# Sheet_CL-STM32.net
KiCad netlist of a schematic drawn in Altium Designer
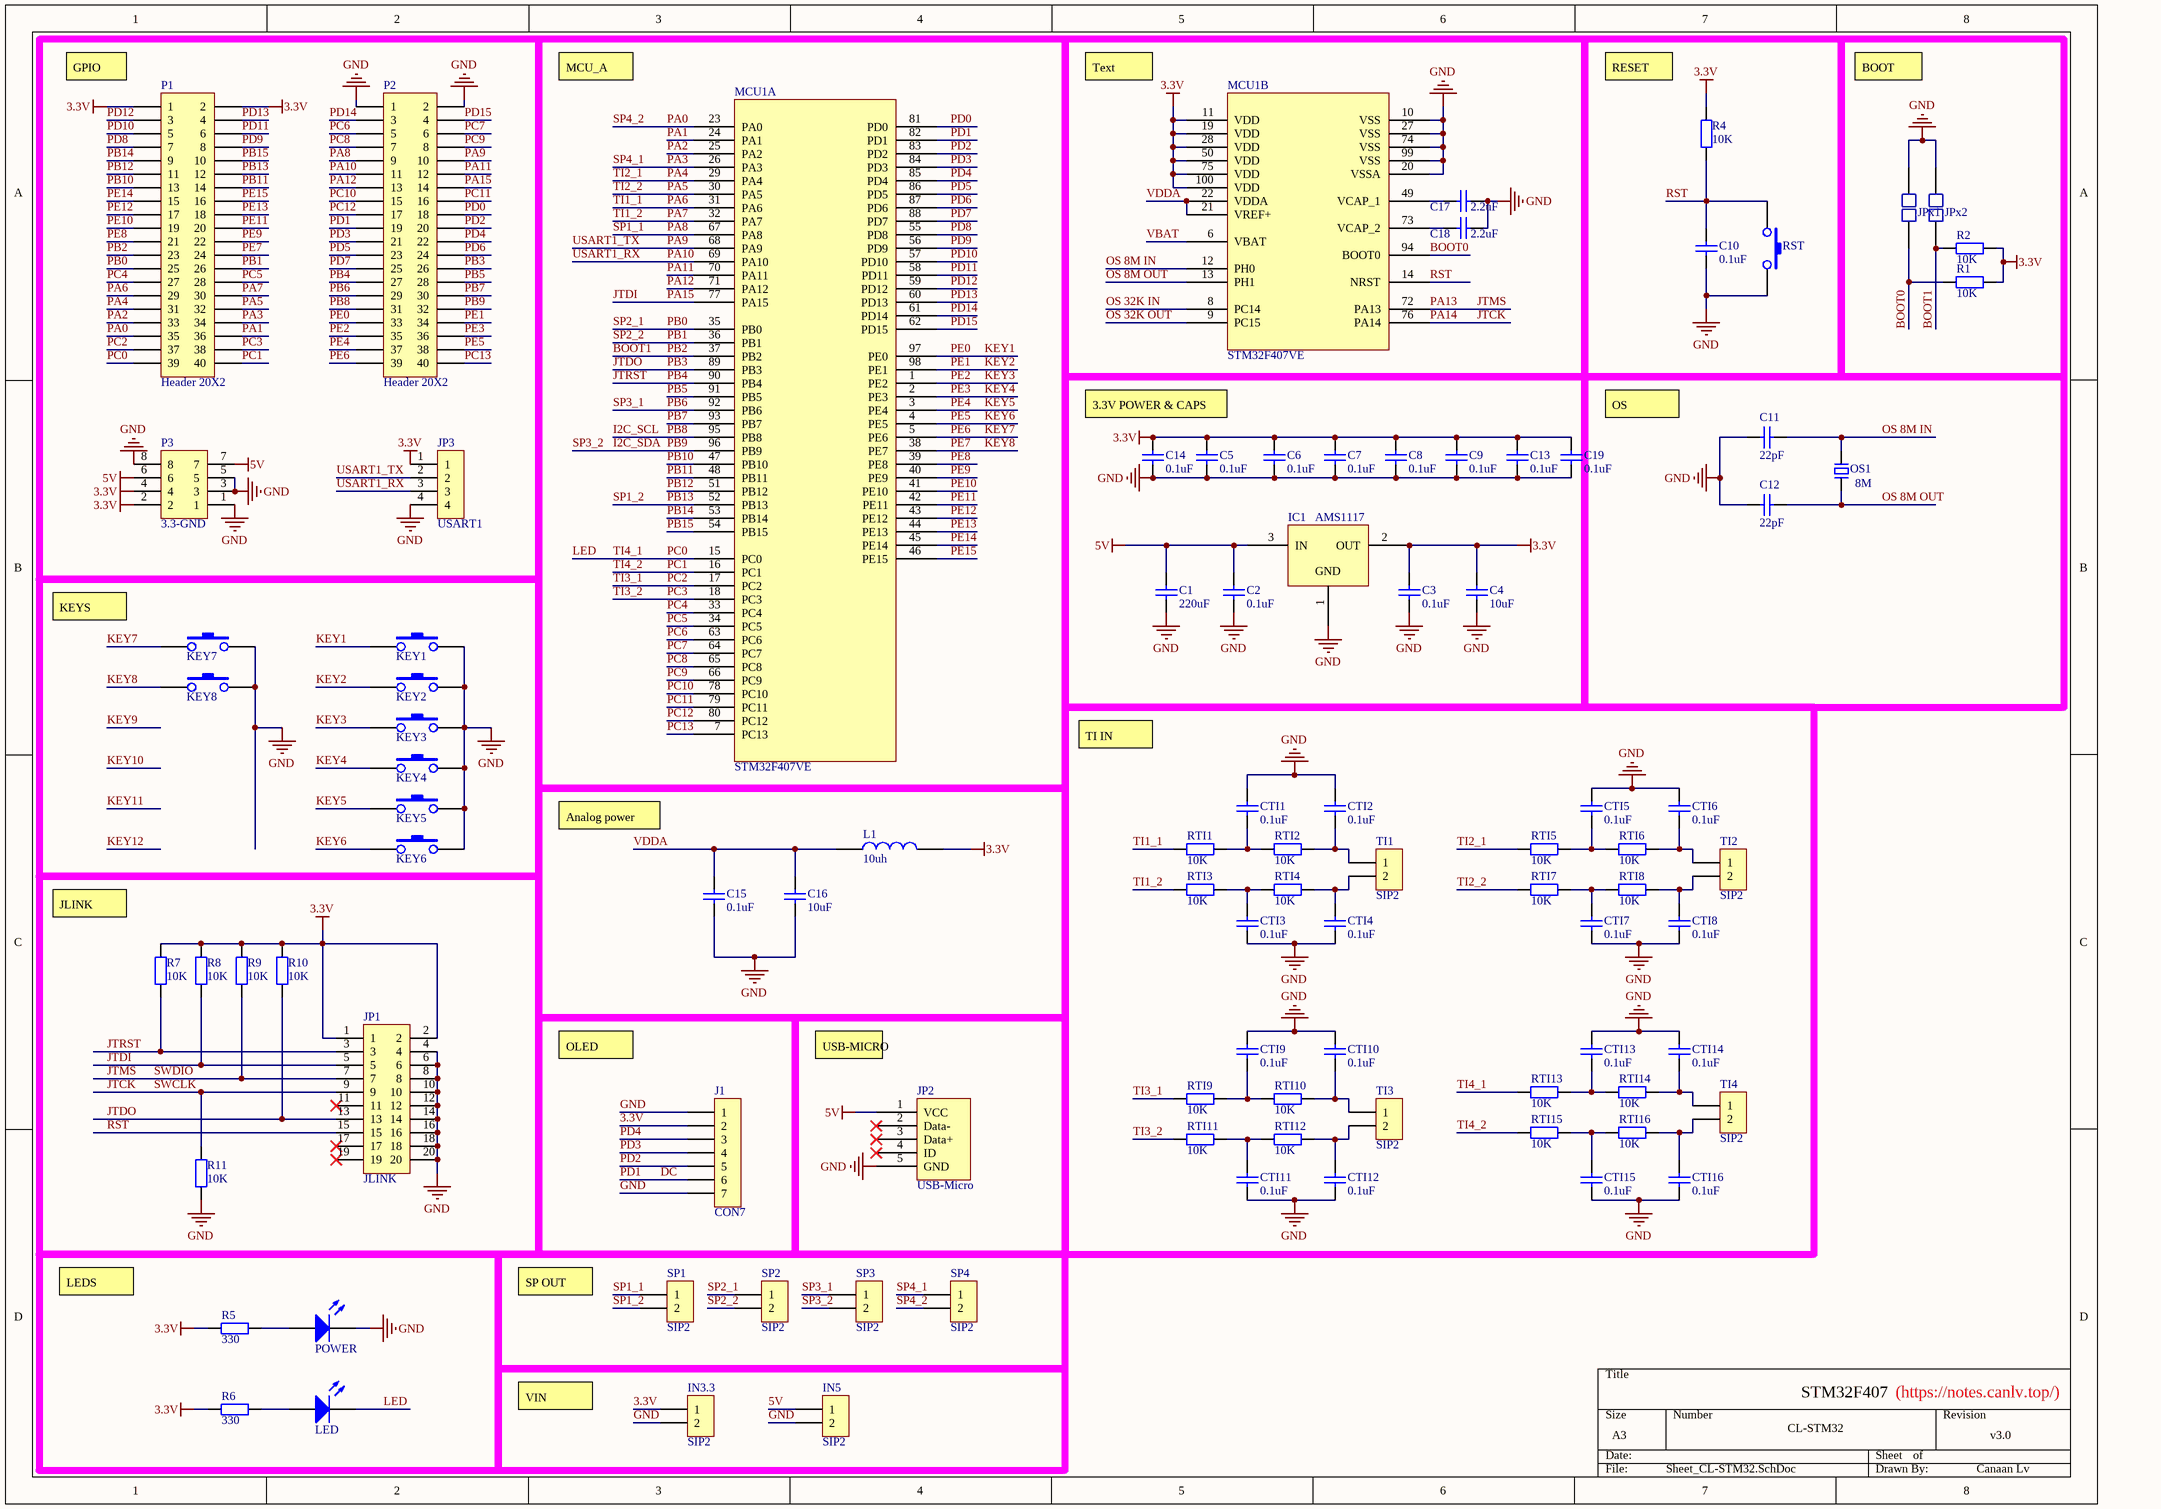
[diagram p0: Sheet_CL-STM32.SchDoc]

(export (version "E")
  (design (tool "Eeschema 10.0.6"))
  (components
    (comp (ref "C1") (value "220uF") (footprint "0805") (libsource (lib "器件库") (part "Cap1")))
    (comp (ref "C2") (value "0.1uF") (footprint "0603") (libsource (lib "器件库") (part "Cap1")))
    (comp (ref "C3") (value "0.1uF") (footprint "0603") (libsource (lib "器件库") (part "Cap1")))
    (comp (ref "C4") (value "10uF") (footprint "0603") (libsource (lib "器件库") (part "Cap1")))
    (comp (ref "C5") (value "0.1uF") (footprint "0603") (libsource (lib "器件库") (part "Cap1")))
    (comp (ref "C6") (value "0.1uF") (footprint "0603") (libsource (lib "器件库") (part "Cap1")))
    (comp (ref "C7") (value "0.1uF") (footprint "0603") (libsource (lib "器件库") (part "Cap1")))
    (comp (ref "C8") (value "0.1uF") (footprint "0603") (libsource (lib "器件库") (part "Cap1")))
    (comp (ref "C9") (value "0.1uF") (footprint "0603") (libsource (lib "器件库") (part "Cap1")))
    (comp (ref "C10") (value "0.1uF") (footprint "0603") (libsource (lib "器件库") (part "Cap1")))
    (comp (ref "C11") (value "22pF") (footprint "0603") (libsource (lib "器件库") (part "Cap1")))
    (comp (ref "C12") (value "22pF") (footprint "0603") (libsource (lib "器件库") (part "Cap1")))
    (comp (ref "C13") (value "0.1uF") (footprint "0603") (libsource (lib "元件") (part "Cap1")))
    (comp (ref "C14") (value "0.1uF") (footprint "0603") (libsource (lib "元件") (part "Cap1")))
    (comp (ref "C15") (value "0.1uF") (footprint "0603") (libsource (lib "器件库") (part "Cap1")))
    (comp (ref "C16") (value "10uF") (footprint "0603") (libsource (lib "器件库") (part "Cap1")))
    (comp (ref "C17") (value "2.2uF") (footprint "0603") (libsource (lib "元件") (part "Cap1")))
    (comp (ref "C18") (value "2.2uF") (footprint "0603") (libsource (lib "元件") (part "Cap1")))
    (comp (ref "C19") (value "0.1uF") (footprint "0603") (libsource (lib "元件") (part "Cap1")))
    (comp (ref "CTI1") (value "0.1uF") (footprint "0603") (libsource (lib "元件") (part "Cap1")))
    (comp (ref "CTI2") (value "0.1uF") (footprint "0603") (libsource (lib "元件") (part "Cap1")))
    (comp (ref "CTI3") (value "0.1uF") (footprint "0603") (libsource (lib "元件") (part "Cap1")))
    (comp (ref "CTI4") (value "0.1uF") (footprint "0603") (libsource (lib "元件") (part "Cap1")))
    (comp (ref "CTI5") (value "0.1uF") (footprint "0603") (libsource (lib "元件") (part "Cap1")))
    (comp (ref "CTI6") (value "0.1uF") (footprint "0603") (libsource (lib "元件") (part "Cap1")))
    (comp (ref "CTI7") (value "0.1uF") (footprint "0603") (libsource (lib "元件") (part "Cap1")))
    (comp (ref "CTI8") (value "0.1uF") (footprint "0603") (libsource (lib "元件") (part "Cap1")))
    (comp (ref "CTI9") (value "0.1uF") (footprint "0603") (libsource (lib "元件") (part "Cap1")))
    (comp (ref "CTI10") (value "0.1uF") (footprint "0603") (libsource (lib "元件") (part "Cap1")))
    (comp (ref "CTI11") (value "0.1uF") (footprint "0603") (libsource (lib "元件") (part "Cap1")))
    (comp (ref "CTI12") (value "0.1uF") (footprint "0603") (libsource (lib "元件") (part "Cap1")))
    (comp (ref "CTI13") (value "0.1uF") (footprint "0603") (libsource (lib "元件") (part "Cap1")))
    (comp (ref "CTI14") (value "0.1uF") (footprint "0603") (libsource (lib "元件") (part "Cap1")))
    (comp (ref "CTI15") (value "0.1uF") (footprint "0603") (libsource (lib "元件") (part "Cap1")))
    (comp (ref "CTI16") (value "0.1uF") (footprint "0603") (libsource (lib "元件") (part "Cap1")))
    (comp (ref "IC1") (value "AMS1117") (footprint "AMS1117") (libsource (lib "器件库") (part "CJA1117")))
    (comp (ref "IN3.3")
      (value "SIP2")
      (footprint "2.54XH接插件2P")
      (description "jointbar")
      (libsource (lib "接口与插座") (part "SIP2"))
    )
    (comp (ref "IN5")
      (value "SIP2")
      (footprint "2.54XH接插件2P")
      (description "jointbar")
      (libsource (lib "接口与插座") (part "SIP2"))
    )
    (comp (ref "J1")
      (value "CON7")
      (footprint "2.54排针1X7")
      (description "Connector")
      (libsource (lib "插件") (part "CON7"))
    )
    (comp (ref "JP1") (value "JLINK") (footprint "2.54简易牛角座20p") (libsource (lib "接插件") (part "PIN-20")))
    (comp (ref "JP2")
      (value "USB-Micro")
      (footprint "USB-MICRO贴片")
      (libsource (lib "接插件") (part "USB-Micro"))
    )
    (comp (ref "JP3") (value "USART1") (footprint "2.54排针1X4") (libsource (lib "接插件") (part "SIP-4")))
    (comp (ref "JPx1") (value "Select") (footprint "选择焊点-0402") (libsource (lib "元件") (part "Select")))
    (comp (ref "JPx2") (value "Select") (footprint "选择焊点-0402") (libsource (lib "元件") (part "Select")))
    (comp (ref "KEY1") (value "按键") (footprint "SWT6*3") (libsource (lib "器件库") (part "按键")))
    (comp (ref "KEY2") (value "按键") (footprint "SWT6*3") (libsource (lib "器件库") (part "按键")))
    (comp (ref "KEY3") (value "按键") (footprint "SWT6*3") (libsource (lib "器件库") (part "按键")))
    (comp (ref "KEY4") (value "按键") (footprint "SWT6*3") (libsource (lib "器件库") (part "按键")))
    (comp (ref "KEY5") (value "按键") (footprint "SWT6*3") (libsource (lib "器件库") (part "按键")))
    (comp (ref "KEY6") (value "按键") (footprint "SWT6*3") (libsource (lib "器件库") (part "按键")))
    (comp (ref "KEY7") (value "按键") (footprint "SWT6*3") (libsource (lib "器件库") (part "按键")))
    (comp (ref "KEY8") (value "按键") (footprint "SWT6*3") (libsource (lib "元件") (part "按键")))
    (comp (ref "L1") (value "10uh") (footprint "0603-res") (libsource (lib "器件库") (part "电感")))
    (comp (ref "LED") (value "LED") (footprint "D0603") (libsource (lib "器件库") (part "LED")))
    (comp (ref "MCU1")
      (value "STM32F407VE")
      (footprint "F-QFP14x14-G100/P.5N")
      (libsource (lib "元件") (part "STM32F407VE"))
    )
    (comp (ref "OS1")
      (value "~")
      (footprint "HC-49S")
      (fields (field (name "ALTIUM_UNNAMED_1") "8M"))
      (libsource (lib "常用2") (part "JT"))
    )
    (comp (ref "P1")
      (value "Header 20X2")
      (footprint "2.54排针2X20")
      (description "Header, 20-Pin, Dual row")
      (fields (field (name "PUBLISHER") "Altium Limited"))
      (libsource (lib "元件") (part "Header 20X2"))
    )
    (comp (ref "P2")
      (value "Header 20X2")
      (footprint "2.54排针2X20")
      (description "Header, 20-Pin, Dual row")
      (fields (field (name "PUBLISHER") "Altium Limited"))
      (libsource (lib "元件") (part "Header 20X2"))
    )
    (comp (ref "P3") (value "3.3-GND") (footprint "2.54排针2X4") (libsource (lib "接插件") (part "PIN-8")))
    (comp (ref "POWER") (value "LED") (footprint "D0603") (libsource (lib "器件库") (part "LED")))
    (comp (ref "R1") (value "10K") (footprint "0603-res") (libsource (lib "") (part "Res_1")))
    (comp (ref "R2") (value "10K") (footprint "0603-res") (libsource (lib "") (part "Res_1")))
    (comp (ref "R4") (value "10K") (footprint "0603-res") (libsource (lib "") (part "Res_1")))
    (comp (ref "R5") (value "330") (footprint "0603-res") (libsource (lib "器件库") (part "Res")))
    (comp (ref "R6") (value "330") (footprint "0603-res") (libsource (lib "器件库") (part "Res")))
    (comp (ref "R7") (value "10K") (footprint "0603-res") (libsource (lib "") (part "Res_1")))
    (comp (ref "R8") (value "10K") (footprint "0603-res") (libsource (lib "") (part "Res_1")))
    (comp (ref "R9") (value "10K") (footprint "0603-res") (libsource (lib "") (part "Res_1")))
    (comp (ref "R10") (value "10K") (footprint "0603-res") (libsource (lib "") (part "Res_1")))
    (comp (ref "R11") (value "10K") (footprint "0603-res") (libsource (lib "") (part "Res_1")))
    (comp (ref "RST") (value "按键") (footprint "按键微动开关2") (libsource (lib "器件库") (part "按键")))
    (comp (ref "RTI1") (value "10K") (footprint "0603-res") (libsource (lib "元件") (part "Res")))
    (comp (ref "RTI2") (value "10K") (footprint "0603-res") (libsource (lib "元件") (part "Res")))
    (comp (ref "RTI3") (value "10K") (footprint "0603-res") (libsource (lib "元件") (part "Res")))
    (comp (ref "RTI4") (value "10K") (footprint "0603-res") (libsource (lib "元件") (part "Res")))
    (comp (ref "RTI5") (value "10K") (footprint "0603-res") (libsource (lib "元件") (part "Res")))
    (comp (ref "RTI6") (value "10K") (footprint "0603-res") (libsource (lib "元件") (part "Res")))
    (comp (ref "RTI7") (value "10K") (footprint "0603-res") (libsource (lib "元件") (part "Res")))
    (comp (ref "RTI8") (value "10K") (footprint "0603-res") (libsource (lib "元件") (part "Res")))
    (comp (ref "RTI9") (value "10K") (footprint "0603-res") (libsource (lib "元件") (part "Res")))
    (comp (ref "RTI10") (value "10K") (footprint "0603-res") (libsource (lib "元件") (part "Res")))
    (comp (ref "RTI11") (value "10K") (footprint "0603-res") (libsource (lib "元件") (part "Res")))
    (comp (ref "RTI12") (value "10K") (footprint "0603-res") (libsource (lib "元件") (part "Res")))
    (comp (ref "RTI13") (value "10K") (footprint "0603-res") (libsource (lib "元件") (part "Res")))
    (comp (ref "RTI14") (value "10K") (footprint "0603-res") (libsource (lib "元件") (part "Res")))
    (comp (ref "RTI15") (value "10K") (footprint "0603-res") (libsource (lib "元件") (part "Res")))
    (comp (ref "RTI16") (value "10K") (footprint "0603-res") (libsource (lib "元件") (part "Res")))
    (comp (ref "SP1")
      (value "SIP2")
      (footprint "2.54XH接插件2P")
      (description "jointbar")
      (libsource (lib "接口与插座") (part "SIP2"))
    )
    (comp (ref "SP2")
      (value "SIP2")
      (footprint "2.54XH接插件2P")
      (description "jointbar")
      (libsource (lib "接口与插座") (part "SIP2"))
    )
    (comp (ref "SP3")
      (value "SIP2")
      (footprint "2.54XH接插件2P")
      (description "jointbar")
      (libsource (lib "接口与插座") (part "SIP2"))
    )
    (comp (ref "SP4")
      (value "SIP2")
      (footprint "2.54XH接插件2P")
      (description "jointbar")
      (libsource (lib "接口与插座") (part "SIP2"))
    )
    (comp (ref "TI1")
      (value "SIP2")
      (footprint "2.54XH接插件2P")
      (description "jointbar")
      (libsource (lib "接口与插座") (part "SIP2"))
    )
    (comp (ref "TI2")
      (value "SIP2")
      (footprint "2.54XH接插件2P")
      (description "jointbar")
      (libsource (lib "接口与插座") (part "SIP2"))
    )
    (comp (ref "TI3")
      (value "SIP2")
      (footprint "2.54XH接插件2P")
      (description "jointbar")
      (libsource (lib "接口与插座") (part "SIP2"))
    )
    (comp (ref "TI4")
      (value "SIP2")
      (footprint "2.54XH接插件2P")
      (description "jointbar")
      (libsource (lib "接口与插座") (part "SIP2"))
    )
  )
  (nets
    (net (code "1") (name "/BOOT0") (class "Default")
      (node (ref "JPx1") (pin "1") (pinfunction "1_1") (pintype "passive"))
      (node (ref "MCU1") (pin "94") (pinfunction "BOOT0_94") (pintype "passive"))
      (node (ref "R1") (pin "2") (pinfunction "2_2") (pintype "passive"))
    )
    (net (code "2") (name "/BOOT1") (class "Default")
      (node (ref "JPx2") (pin "1") (pinfunction "1_1") (pintype "passive"))
      (node (ref "MCU1") (pin "37") (pinfunction "PB2_37") (pintype "passive"))
      (node (ref "P1") (pin "23") (pinfunction "23_23") (pintype "passive"))
      (node (ref "R2") (pin "2") (pinfunction "2_2") (pintype "passive"))
    )
    (net (code "3") (name "/DC") (class "Default")
      (node (ref "J1") (pin "6") (pinfunction "6_6") (pintype "passive"))
      (node (ref "MCU1") (pin "82") (pinfunction "PD1_82") (pintype "passive"))
      (node (ref "P2") (pin "19") (pinfunction "19_19") (pintype "passive"))
    )
    (net (code "4") (name "/I2C_SCL") (class "Default")
      (node (ref "MCU1") (pin "95") (pinfunction "PB8_95") (pintype "passive"))
      (node (ref "P2") (pin "31") (pinfunction "31_31") (pintype "passive"))
    )
    (net (code "5") (name "/I2C_SDA") (class "Default")
      (node (ref "MCU1") (pin "96") (pinfunction "PB9_96") (pintype "passive"))
      (node (ref "P2") (pin "32") (pinfunction "32_32") (pintype "passive"))
      (node (ref "SP3") (pin "2") (pinfunction "2_2") (pintype "passive"))
    )
    (net (code "6") (name "/JTCK") (class "Default")
      (node (ref "JP1") (pin "9") (pinfunction "9_9") (pintype "passive"))
      (node (ref "MCU1") (pin "76") (pinfunction "PA14_76") (pintype "passive"))
      (node (ref "R11") (pin "2") (pinfunction "2_2") (pintype "passive"))
    )
    (net (code "7") (name "/JTDI") (class "Default")
      (node (ref "JP1") (pin "5") (pinfunction "5_5") (pintype "passive"))
      (node (ref "MCU1") (pin "77") (pinfunction "PA15_77") (pintype "passive"))
      (node (ref "P2") (pin "14") (pinfunction "14_14") (pintype "passive"))
      (node (ref "R8") (pin "1") (pinfunction "1_1") (pintype "passive"))
    )
    (net (code "8") (name "/JTDO") (class "Default")
      (node (ref "JP1") (pin "13") (pinfunction "13_13") (pintype "passive"))
      (node (ref "MCU1") (pin "89") (pinfunction "PB3_89") (pintype "passive"))
      (node (ref "P2") (pin "26") (pinfunction "26_26") (pintype "passive"))
      (node (ref "R10") (pin "1") (pinfunction "1_1") (pintype "passive"))
    )
    (net (code "9") (name "/JTMS") (class "Default")
      (node (ref "JP1") (pin "7") (pinfunction "7_7") (pintype "passive"))
      (node (ref "MCU1") (pin "72") (pinfunction "PA13_72") (pintype "passive"))
      (node (ref "R9") (pin "1") (pinfunction "1_1") (pintype "passive"))
    )
    (net (code "10") (name "/JTRST") (class "Default")
      (node (ref "JP1") (pin "3") (pinfunction "3_3") (pintype "passive"))
      (node (ref "MCU1") (pin "90") (pinfunction "PB4_90") (pintype "passive"))
      (node (ref "P2") (pin "27") (pinfunction "27_27") (pintype "passive"))
      (node (ref "R7") (pin "1") (pinfunction "1_1") (pintype "passive"))
    )
    (net (code "11") (name "/KEY1") (class "Default")
      (node (ref "KEY1") (pin "1") (pinfunction "1_1") (pintype "passive"))
      (node (ref "MCU1") (pin "97") (pinfunction "PE0_97") (pintype "passive"))
      (node (ref "P2") (pin "33") (pinfunction "33_33") (pintype "passive"))
    )
    (net (code "12") (name "/KEY2") (class "Default")
      (node (ref "KEY2") (pin "1") (pinfunction "1_1") (pintype "passive"))
      (node (ref "MCU1") (pin "98") (pinfunction "PE1_98") (pintype "passive"))
      (node (ref "P2") (pin "34") (pinfunction "34_34") (pintype "passive"))
    )
    (net (code "13") (name "/KEY3") (class "Default")
      (node (ref "KEY3") (pin "1") (pinfunction "1_1") (pintype "passive"))
      (node (ref "MCU1") (pin "1") (pinfunction "PE2_1") (pintype "passive"))
      (node (ref "P2") (pin "35") (pinfunction "35_35") (pintype "passive"))
    )
    (net (code "14") (name "/KEY4") (class "Default")
      (node (ref "KEY4") (pin "1") (pinfunction "1_1") (pintype "passive"))
      (node (ref "MCU1") (pin "2") (pinfunction "PE3_2") (pintype "passive"))
      (node (ref "P2") (pin "36") (pinfunction "36_36") (pintype "passive"))
    )
    (net (code "15") (name "/KEY5") (class "Default")
      (node (ref "KEY5") (pin "1") (pinfunction "1_1") (pintype "passive"))
      (node (ref "MCU1") (pin "3") (pinfunction "PE4_3") (pintype "passive"))
      (node (ref "P2") (pin "37") (pinfunction "37_37") (pintype "passive"))
    )
    (net (code "16") (name "/KEY6") (class "Default")
      (node (ref "KEY6") (pin "1") (pinfunction "1_1") (pintype "passive"))
      (node (ref "MCU1") (pin "4") (pinfunction "PE5_4") (pintype "passive"))
      (node (ref "P2") (pin "38") (pinfunction "38_38") (pintype "passive"))
    )
    (net (code "17") (name "/KEY7") (class "Default")
      (node (ref "KEY7") (pin "1") (pinfunction "1_1") (pintype "passive"))
      (node (ref "MCU1") (pin "5") (pinfunction "PE6_5") (pintype "passive"))
      (node (ref "P2") (pin "39") (pinfunction "39_39") (pintype "passive"))
    )
    (net (code "18") (name "/KEY8") (class "Default")
      (node (ref "KEY8") (pin "1") (pinfunction "1_1") (pintype "passive"))
      (node (ref "MCU1") (pin "38") (pinfunction "PE7_38") (pintype "passive"))
      (node (ref "P1") (pin "24") (pinfunction "24_24") (pintype "passive"))
    )
    (net (code "23") (name "/LED") (class "Default")
      (node (ref "LED") (pin "2") (pinfunction "K_2") (pintype "passive"))
      (node (ref "MCU1") (pin "15") (pinfunction "PC0_15") (pintype "passive"))
      (node (ref "P1") (pin "39") (pinfunction "39_39") (pintype "passive"))
      (node (ref "RTI13") (pin "1") (pinfunction "1_1") (pintype "passive"))
    )
    (net (code "24") (name "/OS 8M IN") (class "Default")
      (node (ref "C11") (pin "1") (pinfunction "1_1") (pintype "passive"))
      (node (ref "MCU1") (pin "12") (pinfunction "PH0_12") (pintype "passive"))
      (node (ref "OS1") (pin "2") (pinfunction "2_2") (pintype "passive"))
    )
    (net (code "25") (name "/OS 8M OUT") (class "Default")
      (node (ref "C12") (pin "1") (pinfunction "1_1") (pintype "passive"))
      (node (ref "MCU1") (pin "13") (pinfunction "PH1_13") (pintype "passive"))
      (node (ref "OS1") (pin "1") (pinfunction "1_1") (pintype "passive"))
    )
    (net (code "26") (name "/OS 32K IN") (class "Default")
      (node (ref "MCU1") (pin "8") (pinfunction "PC14_8") (pintype "passive"))
    )
    (net (code "27") (name "/OS 32K OUT") (class "Default")
      (node (ref "MCU1") (pin "9") (pinfunction "PC15_9") (pintype "passive"))
    )
    (net (code "28") (name "/PA0") (class "Default")
      (node (ref "MCU1") (pin "23") (pinfunction "PA0_23") (pintype "passive"))
      (node (ref "P1") (pin "35") (pinfunction "35_35") (pintype "passive"))
      (node (ref "SP4") (pin "2") (pinfunction "2_2") (pintype "passive"))
    )
    (net (code "29") (name "/PA1") (class "Default")
      (node (ref "MCU1") (pin "24") (pinfunction "PA1_24") (pintype "passive"))
      (node (ref "P1") (pin "36") (pinfunction "36_36") (pintype "passive"))
    )
    (net (code "30") (name "/PA2") (class "Default")
      (node (ref "MCU1") (pin "25") (pinfunction "PA2_25") (pintype "passive"))
      (node (ref "P1") (pin "33") (pinfunction "33_33") (pintype "passive"))
    )
    (net (code "31") (name "/PA3") (class "Default")
      (node (ref "MCU1") (pin "26") (pinfunction "PA3_26") (pintype "passive"))
      (node (ref "P1") (pin "34") (pinfunction "34_34") (pintype "passive"))
      (node (ref "SP4") (pin "1") (pinfunction "1_1") (pintype "passive"))
    )
    (net (code "32") (name "/PA4") (class "Default")
      (node (ref "MCU1") (pin "29") (pinfunction "PA4_29") (pintype "passive"))
      (node (ref "P1") (pin "31") (pinfunction "31_31") (pintype "passive"))
      (node (ref "RTI5") (pin "1") (pinfunction "1_1") (pintype "passive"))
    )
    (net (code "33") (name "/PA5") (class "Default")
      (node (ref "MCU1") (pin "30") (pinfunction "PA5_30") (pintype "passive"))
      (node (ref "P1") (pin "32") (pinfunction "32_32") (pintype "passive"))
      (node (ref "RTI7") (pin "1") (pinfunction "1_1") (pintype "passive"))
    )
    (net (code "34") (name "/PA6") (class "Default")
      (node (ref "MCU1") (pin "31") (pinfunction "PA6_31") (pintype "passive"))
      (node (ref "P1") (pin "29") (pinfunction "29_29") (pintype "passive"))
      (node (ref "RTI1") (pin "1") (pinfunction "1_1") (pintype "passive"))
    )
    (net (code "35") (name "/PA7") (class "Default")
      (node (ref "MCU1") (pin "32") (pinfunction "PA7_32") (pintype "passive"))
      (node (ref "P1") (pin "30") (pinfunction "30_30") (pintype "passive"))
      (node (ref "RTI3") (pin "1") (pinfunction "1_1") (pintype "passive"))
    )
    (net (code "36") (name "/PA8") (class "Default")
      (node (ref "MCU1") (pin "67") (pinfunction "PA8_67") (pintype "passive"))
      (node (ref "P2") (pin "9") (pinfunction "9_9") (pintype "passive"))
      (node (ref "SP1") (pin "1") (pinfunction "1_1") (pintype "passive"))
    )
    (net (code "37") (name "/PA9") (class "Default")
      (node (ref "JP3") (pin "2") (pinfunction "2_2") (pintype "passive"))
      (node (ref "MCU1") (pin "68") (pinfunction "PA9_68") (pintype "passive"))
      (node (ref "P2") (pin "10") (pinfunction "10_10") (pintype "passive"))
    )
    (net (code "38") (name "/PA10") (class "Default")
      (node (ref "JP3") (pin "3") (pinfunction "3_3") (pintype "passive"))
      (node (ref "MCU1") (pin "69") (pinfunction "PA10_69") (pintype "passive"))
      (node (ref "P2") (pin "11") (pinfunction "11_11") (pintype "passive"))
    )
    (net (code "39") (name "/PA11") (class "Default")
      (node (ref "MCU1") (pin "70") (pinfunction "PA11_70") (pintype "passive"))
      (node (ref "P2") (pin "12") (pinfunction "12_12") (pintype "passive"))
    )
    (net (code "40") (name "/PA12") (class "Default")
      (node (ref "MCU1") (pin "71") (pinfunction "PA12_71") (pintype "passive"))
      (node (ref "P2") (pin "13") (pinfunction "13_13") (pintype "passive"))
    )
    (net (code "41") (name "/PB0") (class "Default")
      (node (ref "MCU1") (pin "35") (pinfunction "PB0_35") (pintype "passive"))
      (node (ref "P1") (pin "25") (pinfunction "25_25") (pintype "passive"))
      (node (ref "SP2") (pin "1") (pinfunction "1_1") (pintype "passive"))
    )
    (net (code "42") (name "/PB1") (class "Default")
      (node (ref "MCU1") (pin "36") (pinfunction "PB1_36") (pintype "passive"))
      (node (ref "P1") (pin "26") (pinfunction "26_26") (pintype "passive"))
      (node (ref "SP2") (pin "2") (pinfunction "2_2") (pintype "passive"))
    )
    (net (code "43") (name "/PB5") (class "Default")
      (node (ref "MCU1") (pin "91") (pinfunction "PB5_91") (pintype "passive"))
      (node (ref "P2") (pin "28") (pinfunction "28_28") (pintype "passive"))
    )
    (net (code "44") (name "/PB6") (class "Default")
      (node (ref "MCU1") (pin "92") (pinfunction "PB6_92") (pintype "passive"))
      (node (ref "P2") (pin "29") (pinfunction "29_29") (pintype "passive"))
      (node (ref "SP3") (pin "1") (pinfunction "1_1") (pintype "passive"))
    )
    (net (code "45") (name "/PB7") (class "Default")
      (node (ref "MCU1") (pin "93") (pinfunction "PB7_93") (pintype "passive"))
      (node (ref "P2") (pin "30") (pinfunction "30_30") (pintype "passive"))
    )
    (net (code "46") (name "/PB10") (class "Default")
      (node (ref "MCU1") (pin "47") (pinfunction "PB10_47") (pintype "passive"))
      (node (ref "P1") (pin "13") (pinfunction "13_13") (pintype "passive"))
    )
    (net (code "47") (name "/PB11") (class "Default")
      (node (ref "MCU1") (pin "48") (pinfunction "PB11_48") (pintype "passive"))
      (node (ref "P1") (pin "14") (pinfunction "14_14") (pintype "passive"))
    )
    (net (code "48") (name "/PB12") (class "Default")
      (node (ref "MCU1") (pin "51") (pinfunction "PB12_51") (pintype "passive"))
      (node (ref "P1") (pin "11") (pinfunction "11_11") (pintype "passive"))
    )
    (net (code "49") (name "/PB13") (class "Default")
      (node (ref "MCU1") (pin "52") (pinfunction "PB13_52") (pintype "passive"))
      (node (ref "P1") (pin "12") (pinfunction "12_12") (pintype "passive"))
      (node (ref "SP1") (pin "2") (pinfunction "2_2") (pintype "passive"))
    )
    (net (code "50") (name "/PB14") (class "Default")
      (node (ref "MCU1") (pin "53") (pinfunction "PB14_53") (pintype "passive"))
      (node (ref "P1") (pin "9") (pinfunction "9_9") (pintype "passive"))
    )
    (net (code "51") (name "/PB15") (class "Default")
      (node (ref "MCU1") (pin "54") (pinfunction "PB15_54") (pintype "passive"))
      (node (ref "P1") (pin "10") (pinfunction "10_10") (pintype "passive"))
    )
    (net (code "52") (name "/PC1") (class "Default")
      (node (ref "MCU1") (pin "16") (pinfunction "PC1_16") (pintype "passive"))
      (node (ref "P1") (pin "40") (pinfunction "40_40") (pintype "passive"))
      (node (ref "RTI15") (pin "1") (pinfunction "1_1") (pintype "passive"))
    )
    (net (code "53") (name "/PC2") (class "Default")
      (node (ref "MCU1") (pin "17") (pinfunction "PC2_17") (pintype "passive"))
      (node (ref "P1") (pin "37") (pinfunction "37_37") (pintype "passive"))
      (node (ref "RTI9") (pin "1") (pinfunction "1_1") (pintype "passive"))
    )
    (net (code "54") (name "/PC3") (class "Default")
      (node (ref "MCU1") (pin "18") (pinfunction "PC3_18") (pintype "passive"))
      (node (ref "P1") (pin "38") (pinfunction "38_38") (pintype "passive"))
      (node (ref "RTI11") (pin "1") (pinfunction "1_1") (pintype "passive"))
    )
    (net (code "55") (name "/PC4") (class "Default")
      (node (ref "MCU1") (pin "33") (pinfunction "PC4_33") (pintype "passive"))
      (node (ref "P1") (pin "27") (pinfunction "27_27") (pintype "passive"))
    )
    (net (code "56") (name "/PC5") (class "Default")
      (node (ref "MCU1") (pin "34") (pinfunction "PC5_34") (pintype "passive"))
      (node (ref "P1") (pin "28") (pinfunction "28_28") (pintype "passive"))
    )
    (net (code "57") (name "/PC6") (class "Default")
      (node (ref "MCU1") (pin "63") (pinfunction "PC6_63") (pintype "passive"))
      (node (ref "P2") (pin "5") (pinfunction "5_5") (pintype "passive"))
    )
    (net (code "58") (name "/PC7") (class "Default")
      (node (ref "MCU1") (pin "64") (pinfunction "PC7_64") (pintype "passive"))
      (node (ref "P2") (pin "6") (pinfunction "6_6") (pintype "passive"))
    )
    (net (code "59") (name "/PC8") (class "Default")
      (node (ref "MCU1") (pin "65") (pinfunction "PC8_65") (pintype "passive"))
      (node (ref "P2") (pin "7") (pinfunction "7_7") (pintype "passive"))
    )
    (net (code "60") (name "/PC9") (class "Default")
      (node (ref "MCU1") (pin "66") (pinfunction "PC9_66") (pintype "passive"))
      (node (ref "P2") (pin "8") (pinfunction "8_8") (pintype "passive"))
    )
    (net (code "61") (name "/PC10") (class "Default")
      (node (ref "MCU1") (pin "78") (pinfunction "PC10_78") (pintype "passive"))
      (node (ref "P2") (pin "15") (pinfunction "15_15") (pintype "passive"))
    )
    (net (code "62") (name "/PC11") (class "Default")
      (node (ref "MCU1") (pin "79") (pinfunction "PC11_79") (pintype "passive"))
      (node (ref "P2") (pin "16") (pinfunction "16_16") (pintype "passive"))
    )
    (net (code "63") (name "/PC12") (class "Default")
      (node (ref "MCU1") (pin "80") (pinfunction "PC12_80") (pintype "passive"))
      (node (ref "P2") (pin "17") (pinfunction "17_17") (pintype "passive"))
    )
    (net (code "64") (name "/PC13") (class "Default")
      (node (ref "MCU1") (pin "7") (pinfunction "PC13_7") (pintype "passive"))
      (node (ref "P2") (pin "40") (pinfunction "40_40") (pintype "passive"))
    )
    (net (code "65") (name "/PD0") (class "Default")
      (node (ref "MCU1") (pin "81") (pinfunction "PD0_81") (pintype "passive"))
      (node (ref "P2") (pin "18") (pinfunction "18_18") (pintype "passive"))
    )
    (net (code "66") (name "/PD2") (class "Default")
      (node (ref "J1") (pin "5") (pinfunction "5_5") (pintype "passive"))
      (node (ref "MCU1") (pin "83") (pinfunction "PD2_83") (pintype "passive"))
      (node (ref "P2") (pin "20") (pinfunction "20_20") (pintype "passive"))
    )
    (net (code "67") (name "/PD3") (class "Default")
      (node (ref "J1") (pin "4") (pinfunction "4_4") (pintype "passive"))
      (node (ref "MCU1") (pin "84") (pinfunction "PD3_84") (pintype "passive"))
      (node (ref "P2") (pin "21") (pinfunction "21_21") (pintype "passive"))
    )
    (net (code "68") (name "/PD4") (class "Default")
      (node (ref "J1") (pin "3") (pinfunction "3_3") (pintype "passive"))
      (node (ref "MCU1") (pin "85") (pinfunction "PD4_85") (pintype "passive"))
      (node (ref "P2") (pin "22") (pinfunction "22_22") (pintype "passive"))
    )
    (net (code "69") (name "/PD5") (class "Default")
      (node (ref "MCU1") (pin "86") (pinfunction "PD5_86") (pintype "passive"))
      (node (ref "P2") (pin "23") (pinfunction "23_23") (pintype "passive"))
    )
    (net (code "70") (name "/PD6") (class "Default")
      (node (ref "MCU1") (pin "87") (pinfunction "PD6_87") (pintype "passive"))
      (node (ref "P2") (pin "24") (pinfunction "24_24") (pintype "passive"))
    )
    (net (code "71") (name "/PD7") (class "Default")
      (node (ref "MCU1") (pin "88") (pinfunction "PD7_88") (pintype "passive"))
      (node (ref "P2") (pin "25") (pinfunction "25_25") (pintype "passive"))
    )
    (net (code "72") (name "/PD8") (class "Default")
      (node (ref "MCU1") (pin "55") (pinfunction "PD8_55") (pintype "passive"))
      (node (ref "P1") (pin "7") (pinfunction "7_7") (pintype "passive"))
    )
    (net (code "73") (name "/PD9") (class "Default")
      (node (ref "MCU1") (pin "56") (pinfunction "PD9_56") (pintype "passive"))
      (node (ref "P1") (pin "8") (pinfunction "8_8") (pintype "passive"))
    )
    (net (code "74") (name "/PD10") (class "Default")
      (node (ref "MCU1") (pin "57") (pinfunction "PD10_57") (pintype "passive"))
      (node (ref "P1") (pin "5") (pinfunction "5_5") (pintype "passive"))
    )
    (net (code "75") (name "/PD11") (class "Default")
      (node (ref "MCU1") (pin "58") (pinfunction "PD11_58") (pintype "passive"))
      (node (ref "P1") (pin "6") (pinfunction "6_6") (pintype "passive"))
    )
    (net (code "76") (name "/PD12") (class "Default")
      (node (ref "MCU1") (pin "59") (pinfunction "PD12_59") (pintype "passive"))
      (node (ref "P1") (pin "3") (pinfunction "3_3") (pintype "passive"))
    )
    (net (code "77") (name "/PD13") (class "Default")
      (node (ref "MCU1") (pin "60") (pinfunction "PD13_60") (pintype "passive"))
      (node (ref "P1") (pin "4") (pinfunction "4_4") (pintype "passive"))
    )
    (net (code "78") (name "/PD14") (class "Default")
      (node (ref "MCU1") (pin "61") (pinfunction "PD14_61") (pintype "passive"))
      (node (ref "P2") (pin "3") (pinfunction "3_3") (pintype "passive"))
    )
    (net (code "79") (name "/PD15") (class "Default")
      (node (ref "MCU1") (pin "62") (pinfunction "PD15_62") (pintype "passive"))
      (node (ref "P2") (pin "4") (pinfunction "4_4") (pintype "passive"))
    )
    (net (code "80") (name "/PE8") (class "Default")
      (node (ref "MCU1") (pin "39") (pinfunction "PE8_39") (pintype "passive"))
      (node (ref "P1") (pin "21") (pinfunction "21_21") (pintype "passive"))
    )
    (net (code "81") (name "/PE9") (class "Default")
      (node (ref "MCU1") (pin "40") (pinfunction "PE9_40") (pintype "passive"))
      (node (ref "P1") (pin "22") (pinfunction "22_22") (pintype "passive"))
    )
    (net (code "82") (name "/PE10") (class "Default")
      (node (ref "MCU1") (pin "41") (pinfunction "PE10_41") (pintype "passive"))
      (node (ref "P1") (pin "19") (pinfunction "19_19") (pintype "passive"))
    )
    (net (code "83") (name "/PE11") (class "Default")
      (node (ref "MCU1") (pin "42") (pinfunction "PE11_42") (pintype "passive"))
      (node (ref "P1") (pin "20") (pinfunction "20_20") (pintype "passive"))
    )
    (net (code "84") (name "/PE12") (class "Default")
      (node (ref "MCU1") (pin "43") (pinfunction "PE12_43") (pintype "passive"))
      (node (ref "P1") (pin "17") (pinfunction "17_17") (pintype "passive"))
    )
    (net (code "85") (name "/PE13") (class "Default")
      (node (ref "MCU1") (pin "44") (pinfunction "PE13_44") (pintype "passive"))
      (node (ref "P1") (pin "18") (pinfunction "18_18") (pintype "passive"))
    )
    (net (code "86") (name "/PE14") (class "Default")
      (node (ref "MCU1") (pin "45") (pinfunction "PE14_45") (pintype "passive"))
      (node (ref "P1") (pin "15") (pinfunction "15_15") (pintype "passive"))
    )
    (net (code "87") (name "/PE15") (class "Default")
      (node (ref "MCU1") (pin "46") (pinfunction "PE15_46") (pintype "passive"))
      (node (ref "P1") (pin "16") (pinfunction "16_16") (pintype "passive"))
    )
    (net (code "88") (name "/RST") (class "Default")
      (node (ref "C10") (pin "2") (pinfunction "2_2") (pintype "passive"))
      (node (ref "JP1") (pin "15") (pinfunction "15_15") (pintype "passive"))
      (node (ref "MCU1") (pin "14") (pinfunction "NRST_14") (pintype "passive"))
      (node (ref "R4") (pin "1") (pinfunction "1_1") (pintype "passive"))
      (node (ref "RST") (pin "1") (pinfunction "1_1") (pintype "passive"))
    )
    (net (code "89") (name "/VBAT") (class "Default")
      (node (ref "MCU1") (pin "6") (pinfunction "VBAT_6") (pintype "passive"))
    )
    (net (code "90") (name "/VDDA") (class "Default")
      (node (ref "C15") (pin "2") (pinfunction "2_2") (pintype "passive"))
      (node (ref "C16") (pin "2") (pinfunction "2_2") (pintype "passive"))
      (node (ref "L1") (pin "1") (pinfunction "1_1") (pintype "passive"))
      (node (ref "MCU1") (pin "21") (pinfunction "VREF+_21") (pintype "passive"))
      (node (ref "MCU1") (pin "22") (pinfunction "VDDA_22") (pintype "passive"))
    )
    (net (code "91") (name "3.3V") (class "Default")
      (node (ref "C13") (pin "2") (pinfunction "2_2") (pintype "passive"))
      (node (ref "C14") (pin "2") (pinfunction "2_2") (pintype "passive"))
      (node (ref "C19") (pin "2") (pinfunction "2_2") (pintype "passive"))
      (node (ref "C3") (pin "2") (pinfunction "2_2") (pintype "passive"))
      (node (ref "C4") (pin "2") (pinfunction "2_2") (pintype "passive"))
      (node (ref "C5") (pin "2") (pinfunction "2_2") (pintype "passive"))
      (node (ref "C6") (pin "2") (pinfunction "2_2") (pintype "passive"))
      (node (ref "C7") (pin "2") (pinfunction "2_2") (pintype "passive"))
      (node (ref "C8") (pin "2") (pinfunction "2_2") (pintype "passive"))
      (node (ref "C9") (pin "2") (pinfunction "2_2") (pintype "passive"))
      (node (ref "IC1") (pin "2") (pinfunction "OUT_2") (pintype "passive"))
      (node (ref "IN3.3") (pin "1") (pinfunction "1_1") (pintype "passive"))
      (node (ref "J1") (pin "2") (pinfunction "2_2") (pintype "passive"))
      (node (ref "JP1") (pin "1") (pinfunction "1_1") (pintype "passive"))
      (node (ref "JP1") (pin "2") (pinfunction "2_2") (pintype "passive"))
      (node (ref "JP3") (pin "1") (pinfunction "1_1") (pintype "passive"))
      (node (ref "L1") (pin "2") (pinfunction "2_2") (pintype "passive"))
      (node (ref "MCU1") (pin "100") (pinfunction "VDD_100") (pintype "passive"))
      (node (ref "MCU1") (pin "11") (pinfunction "VDD_11") (pintype "passive"))
      (node (ref "MCU1") (pin "19") (pinfunction "VDD_19") (pintype "passive"))
      (node (ref "MCU1") (pin "28") (pinfunction "VDD_28") (pintype "passive"))
      (node (ref "MCU1") (pin "50") (pinfunction "VDD_50") (pintype "passive"))
      (node (ref "MCU1") (pin "75") (pinfunction "VDD_75") (pintype "passive"))
      (node (ref "P1") (pin "1") (pinfunction "1_1") (pintype "passive"))
      (node (ref "P1") (pin "2") (pinfunction "2_2") (pintype "passive"))
      (node (ref "P3") (pin "2") (pinfunction "2_2") (pintype "passive"))
      (node (ref "P3") (pin "4") (pinfunction "4_4") (pintype "passive"))
      (node (ref "R1") (pin "1") (pinfunction "1_1") (pintype "passive"))
      (node (ref "R10") (pin "2") (pinfunction "2_2") (pintype "passive"))
      (node (ref "R2") (pin "1") (pinfunction "1_1") (pintype "passive"))
      (node (ref "R4") (pin "2") (pinfunction "2_2") (pintype "passive"))
      (node (ref "R5") (pin "1") (pinfunction "1_1") (pintype "passive"))
      (node (ref "R6") (pin "1") (pinfunction "1_1") (pintype "passive"))
      (node (ref "R7") (pin "2") (pinfunction "2_2") (pintype "passive"))
      (node (ref "R8") (pin "2") (pinfunction "2_2") (pintype "passive"))
      (node (ref "R9") (pin "2") (pinfunction "2_2") (pintype "passive"))
    )
    (net (code "92") (name "5V") (class "Default")
      (node (ref "C1") (pin "2") (pinfunction "2_2") (pintype "passive"))
      (node (ref "C2") (pin "2") (pinfunction "2_2") (pintype "passive"))
      (node (ref "IC1") (pin "3") (pinfunction "IN_3") (pintype "passive"))
      (node (ref "IN5") (pin "1") (pinfunction "1_1") (pintype "passive"))
      (node (ref "JP2") (pin "1") (pinfunction "VCC_1") (pintype "passive"))
      (node (ref "P3") (pin "6") (pinfunction "6_6") (pintype "passive"))
      (node (ref "P3") (pin "7") (pinfunction "7_7") (pintype "passive"))
    )
    (net (code "93") (name "GND") (class "Default")
      (node (ref "C1") (pin "1") (pinfunction "1_1") (pintype "passive"))
      (node (ref "C10") (pin "1") (pinfunction "1_1") (pintype "passive"))
      (node (ref "C11") (pin "2") (pinfunction "2_2") (pintype "passive"))
      (node (ref "C12") (pin "2") (pinfunction "2_2") (pintype "passive"))
      (node (ref "C13") (pin "1") (pinfunction "1_1") (pintype "passive"))
      (node (ref "C14") (pin "1") (pinfunction "1_1") (pintype "passive"))
      (node (ref "C15") (pin "1") (pinfunction "1_1") (pintype "passive"))
      (node (ref "C16") (pin "1") (pinfunction "1_1") (pintype "passive"))
      (node (ref "C17") (pin "2") (pinfunction "2_2") (pintype "passive"))
      (node (ref "C18") (pin "2") (pinfunction "2_2") (pintype "passive"))
      (node (ref "C19") (pin "1") (pinfunction "1_1") (pintype "passive"))
      (node (ref "C2") (pin "1") (pinfunction "1_1") (pintype "passive"))
      (node (ref "C3") (pin "1") (pinfunction "1_1") (pintype "passive"))
      (node (ref "C4") (pin "1") (pinfunction "1_1") (pintype "passive"))
      (node (ref "C5") (pin "1") (pinfunction "1_1") (pintype "passive"))
      (node (ref "C6") (pin "1") (pinfunction "1_1") (pintype "passive"))
      (node (ref "C7") (pin "1") (pinfunction "1_1") (pintype "passive"))
      (node (ref "C8") (pin "1") (pinfunction "1_1") (pintype "passive"))
      (node (ref "C9") (pin "1") (pinfunction "1_1") (pintype "passive"))
      (node (ref "CTI1") (pin "2") (pinfunction "2_2") (pintype "passive"))
      (node (ref "CTI10") (pin "2") (pinfunction "2_2") (pintype "passive"))
      (node (ref "CTI11") (pin "1") (pinfunction "1_1") (pintype "passive"))
      (node (ref "CTI12") (pin "1") (pinfunction "1_1") (pintype "passive"))
      (node (ref "CTI13") (pin "2") (pinfunction "2_2") (pintype "passive"))
      (node (ref "CTI14") (pin "2") (pinfunction "2_2") (pintype "passive"))
      (node (ref "CTI15") (pin "1") (pinfunction "1_1") (pintype "passive"))
      (node (ref "CTI16") (pin "1") (pinfunction "1_1") (pintype "passive"))
      (node (ref "CTI2") (pin "2") (pinfunction "2_2") (pintype "passive"))
      (node (ref "CTI3") (pin "1") (pinfunction "1_1") (pintype "passive"))
      (node (ref "CTI4") (pin "1") (pinfunction "1_1") (pintype "passive"))
      (node (ref "CTI5") (pin "2") (pinfunction "2_2") (pintype "passive"))
      (node (ref "CTI6") (pin "2") (pinfunction "2_2") (pintype "passive"))
      (node (ref "CTI7") (pin "1") (pinfunction "1_1") (pintype "passive"))
      (node (ref "CTI8") (pin "1") (pinfunction "1_1") (pintype "passive"))
      (node (ref "CTI9") (pin "2") (pinfunction "2_2") (pintype "passive"))
      (node (ref "IC1") (pin "1") (pinfunction "GND_1") (pintype "passive"))
      (node (ref "IN3.3") (pin "2") (pinfunction "2_2") (pintype "passive"))
      (node (ref "IN5") (pin "2") (pinfunction "2_2") (pintype "passive"))
      (node (ref "J1") (pin "1") (pinfunction "1_1") (pintype "passive"))
      (node (ref "J1") (pin "7") (pinfunction "7_7") (pintype "passive"))
      (node (ref "JP1") (pin "10") (pinfunction "10_10") (pintype "passive"))
      (node (ref "JP1") (pin "12") (pinfunction "12_12") (pintype "passive"))
      (node (ref "JP1") (pin "14") (pinfunction "14_14") (pintype "passive"))
      (node (ref "JP1") (pin "16") (pinfunction "16_16") (pintype "passive"))
      (node (ref "JP1") (pin "18") (pinfunction "18_18") (pintype "passive"))
      (node (ref "JP1") (pin "20") (pinfunction "20_20") (pintype "passive"))
      (node (ref "JP1") (pin "4") (pinfunction "4_4") (pintype "passive"))
      (node (ref "JP1") (pin "6") (pinfunction "6_6") (pintype "passive"))
      (node (ref "JP1") (pin "8") (pinfunction "8_8") (pintype "passive"))
      (node (ref "JP2") (pin "5") (pinfunction "GND_5") (pintype "passive"))
      (node (ref "JP3") (pin "4") (pinfunction "4_4") (pintype "passive"))
      (node (ref "JPx1") (pin "2") (pinfunction "2_2") (pintype "passive"))
      (node (ref "JPx2") (pin "2") (pinfunction "2_2") (pintype "passive"))
      (node (ref "KEY1") (pin "2") (pinfunction "2_2") (pintype "passive"))
      (node (ref "KEY2") (pin "2") (pinfunction "2_2") (pintype "passive"))
      (node (ref "KEY3") (pin "2") (pinfunction "2_2") (pintype "passive"))
      (node (ref "KEY4") (pin "2") (pinfunction "2_2") (pintype "passive"))
      (node (ref "KEY5") (pin "2") (pinfunction "2_2") (pintype "passive"))
      (node (ref "KEY6") (pin "2") (pinfunction "2_2") (pintype "passive"))
      (node (ref "KEY7") (pin "2") (pinfunction "2_2") (pintype "passive"))
      (node (ref "KEY8") (pin "2") (pinfunction "2_2") (pintype "passive"))
      (node (ref "MCU1") (pin "10") (pinfunction "VSS_10") (pintype "passive"))
      (node (ref "MCU1") (pin "20") (pinfunction "VSSA_20") (pintype "passive"))
      (node (ref "MCU1") (pin "27") (pinfunction "VSS_27") (pintype "passive"))
      (node (ref "MCU1") (pin "74") (pinfunction "VSS_74") (pintype "passive"))
      (node (ref "MCU1") (pin "99") (pinfunction "VSS_99") (pintype "passive"))
      (node (ref "P2") (pin "1") (pinfunction "1_1") (pintype "passive"))
      (node (ref "P2") (pin "2") (pinfunction "2_2") (pintype "passive"))
      (node (ref "P3") (pin "1") (pinfunction "1_1") (pintype "passive"))
      (node (ref "P3") (pin "3") (pinfunction "3_3") (pintype "passive"))
      (node (ref "P3") (pin "5") (pinfunction "5_5") (pintype "passive"))
      (node (ref "P3") (pin "8") (pinfunction "8_8") (pintype "passive"))
      (node (ref "POWER") (pin "2") (pinfunction "K_2") (pintype "passive"))
      (node (ref "R11") (pin "1") (pinfunction "1_1") (pintype "passive"))
      (node (ref "RST") (pin "2") (pinfunction "2_2") (pintype "passive"))
    )
    (net (code "94") (name "Net-(CTI1-Pad1)") (class "Default")
      (node (ref "CTI1") (pin "1") (pinfunction "1_1") (pintype "passive"))
      (node (ref "RTI1") (pin "2") (pinfunction "2_2") (pintype "passive"))
      (node (ref "RTI2") (pin "1") (pinfunction "1_1") (pintype "passive"))
    )
    (net (code "95") (name "Net-(CTI2-Pad1)") (class "Default")
      (node (ref "CTI2") (pin "1") (pinfunction "1_1") (pintype "passive"))
      (node (ref "RTI2") (pin "2") (pinfunction "2_2") (pintype "passive"))
      (node (ref "TI1") (pin "1") (pinfunction "1_1") (pintype "passive"))
    )
    (net (code "96") (name "Net-(CTI3-Pad2)") (class "Default")
      (node (ref "CTI3") (pin "2") (pinfunction "2_2") (pintype "passive"))
      (node (ref "RTI3") (pin "2") (pinfunction "2_2") (pintype "passive"))
      (node (ref "RTI4") (pin "1") (pinfunction "1_1") (pintype "passive"))
    )
    (net (code "97") (name "Net-(CTI4-Pad2)") (class "Default")
      (node (ref "CTI4") (pin "2") (pinfunction "2_2") (pintype "passive"))
      (node (ref "RTI4") (pin "2") (pinfunction "2_2") (pintype "passive"))
      (node (ref "TI1") (pin "2") (pinfunction "2_2") (pintype "passive"))
    )
    (net (code "98") (name "Net-(CTI5-Pad1)") (class "Default")
      (node (ref "CTI5") (pin "1") (pinfunction "1_1") (pintype "passive"))
      (node (ref "RTI5") (pin "2") (pinfunction "2_2") (pintype "passive"))
      (node (ref "RTI6") (pin "1") (pinfunction "1_1") (pintype "passive"))
    )
    (net (code "99") (name "Net-(CTI6-Pad1)") (class "Default")
      (node (ref "CTI6") (pin "1") (pinfunction "1_1") (pintype "passive"))
      (node (ref "RTI6") (pin "2") (pinfunction "2_2") (pintype "passive"))
      (node (ref "TI2") (pin "1") (pinfunction "1_1") (pintype "passive"))
    )
    (net (code "100") (name "Net-(CTI7-Pad2)") (class "Default")
      (node (ref "CTI7") (pin "2") (pinfunction "2_2") (pintype "passive"))
      (node (ref "RTI7") (pin "2") (pinfunction "2_2") (pintype "passive"))
      (node (ref "RTI8") (pin "1") (pinfunction "1_1") (pintype "passive"))
    )
    (net (code "101") (name "Net-(CTI8-Pad2)") (class "Default")
      (node (ref "CTI8") (pin "2") (pinfunction "2_2") (pintype "passive"))
      (node (ref "RTI8") (pin "2") (pinfunction "2_2") (pintype "passive"))
      (node (ref "TI2") (pin "2") (pinfunction "2_2") (pintype "passive"))
    )
    (net (code "102") (name "Net-(CTI9-Pad1)") (class "Default")
      (node (ref "CTI9") (pin "1") (pinfunction "1_1") (pintype "passive"))
      (node (ref "RTI10") (pin "1") (pinfunction "1_1") (pintype "passive"))
      (node (ref "RTI9") (pin "2") (pinfunction "2_2") (pintype "passive"))
    )
    (net (code "103") (name "Net-(CTI10-Pad1)") (class "Default")
      (node (ref "CTI10") (pin "1") (pinfunction "1_1") (pintype "passive"))
      (node (ref "RTI10") (pin "2") (pinfunction "2_2") (pintype "passive"))
      (node (ref "TI3") (pin "1") (pinfunction "1_1") (pintype "passive"))
    )
    (net (code "104") (name "Net-(CTI11-Pad2)") (class "Default")
      (node (ref "CTI11") (pin "2") (pinfunction "2_2") (pintype "passive"))
      (node (ref "RTI11") (pin "2") (pinfunction "2_2") (pintype "passive"))
      (node (ref "RTI12") (pin "1") (pinfunction "1_1") (pintype "passive"))
    )
    (net (code "105") (name "Net-(CTI12-Pad2)") (class "Default")
      (node (ref "CTI12") (pin "2") (pinfunction "2_2") (pintype "passive"))
      (node (ref "RTI12") (pin "2") (pinfunction "2_2") (pintype "passive"))
      (node (ref "TI3") (pin "2") (pinfunction "2_2") (pintype "passive"))
    )
    (net (code "106") (name "Net-(CTI13-Pad1)") (class "Default")
      (node (ref "CTI13") (pin "1") (pinfunction "1_1") (pintype "passive"))
      (node (ref "RTI13") (pin "2") (pinfunction "2_2") (pintype "passive"))
      (node (ref "RTI14") (pin "1") (pinfunction "1_1") (pintype "passive"))
    )
    (net (code "107") (name "Net-(CTI14-Pad1)") (class "Default")
      (node (ref "CTI14") (pin "1") (pinfunction "1_1") (pintype "passive"))
      (node (ref "RTI14") (pin "2") (pinfunction "2_2") (pintype "passive"))
      (node (ref "TI4") (pin "1") (pinfunction "1_1") (pintype "passive"))
    )
    (net (code "108") (name "Net-(CTI15-Pad2)") (class "Default")
      (node (ref "CTI15") (pin "2") (pinfunction "2_2") (pintype "passive"))
      (node (ref "RTI15") (pin "2") (pinfunction "2_2") (pintype "passive"))
      (node (ref "RTI16") (pin "1") (pinfunction "1_1") (pintype "passive"))
    )
    (net (code "109") (name "Net-(CTI16-Pad2)") (class "Default")
      (node (ref "CTI16") (pin "2") (pinfunction "2_2") (pintype "passive"))
      (node (ref "RTI16") (pin "2") (pinfunction "2_2") (pintype "passive"))
      (node (ref "TI4") (pin "2") (pinfunction "2_2") (pintype "passive"))
    )
    (net (code "110") (name "Net-(LED-A)") (class "Default")
      (node (ref "LED") (pin "1") (pinfunction "A_1") (pintype "passive"))
      (node (ref "R6") (pin "2") (pinfunction "2_2") (pintype "passive"))
    )
    (net (code "111") (name "Net-(MCU1B-VCAP_1)") (class "Default")
      (node (ref "C17") (pin "1") (pinfunction "1_1") (pintype "passive"))
      (node (ref "MCU1") (pin "49") (pinfunction "VCAP_1_49") (pintype "passive"))
    )
    (net (code "112") (name "Net-(MCU1B-VCAP_2)") (class "Default")
      (node (ref "C18") (pin "1") (pinfunction "1_1") (pintype "passive"))
      (node (ref "MCU1") (pin "73") (pinfunction "VCAP_2_73") (pintype "passive"))
    )
    (net (code "113") (name "Net-(POWER-A)") (class "Default")
      (node (ref "POWER") (pin "1") (pinfunction "A_1") (pintype "passive"))
      (node (ref "R5") (pin "2") (pinfunction "2_2") (pintype "passive"))
    )
    (net (code "114") (name "unconnected-(JP1-Pad11)") (class "Default")
      (node (ref "JP1") (pin "11") (pinfunction "11_11") (pintype "passive+no_connect"))
    )
    (net (code "115") (name "unconnected-(JP1-Pad17)") (class "Default")
      (node (ref "JP1") (pin "17") (pinfunction "17_17") (pintype "passive+no_connect"))
    )
    (net (code "116") (name "unconnected-(JP1-Pad19)") (class "Default")
      (node (ref "JP1") (pin "19") (pinfunction "19_19") (pintype "passive+no_connect"))
    )
    (net (code "117") (name "unconnected-(JP2-Data+-Pad3)") (class "Default")
      (node (ref "JP2") (pin "3") (pinfunction "Data+_3") (pintype "passive+no_connect"))
    )
    (net (code "118") (name "unconnected-(JP2-Data--Pad2)") (class "Default")
      (node (ref "JP2") (pin "2") (pinfunction "Data-_2") (pintype "passive+no_connect"))
    )
    (net (code "119") (name "unconnected-(JP2-ID-Pad4)") (class "Default")
      (node (ref "JP2") (pin "4") (pinfunction "ID_4") (pintype "passive+no_connect"))
    )
  )
)
